# 2_4G8_2.net
KiCad netlist of a schematic drawn in EasyEDA Pro
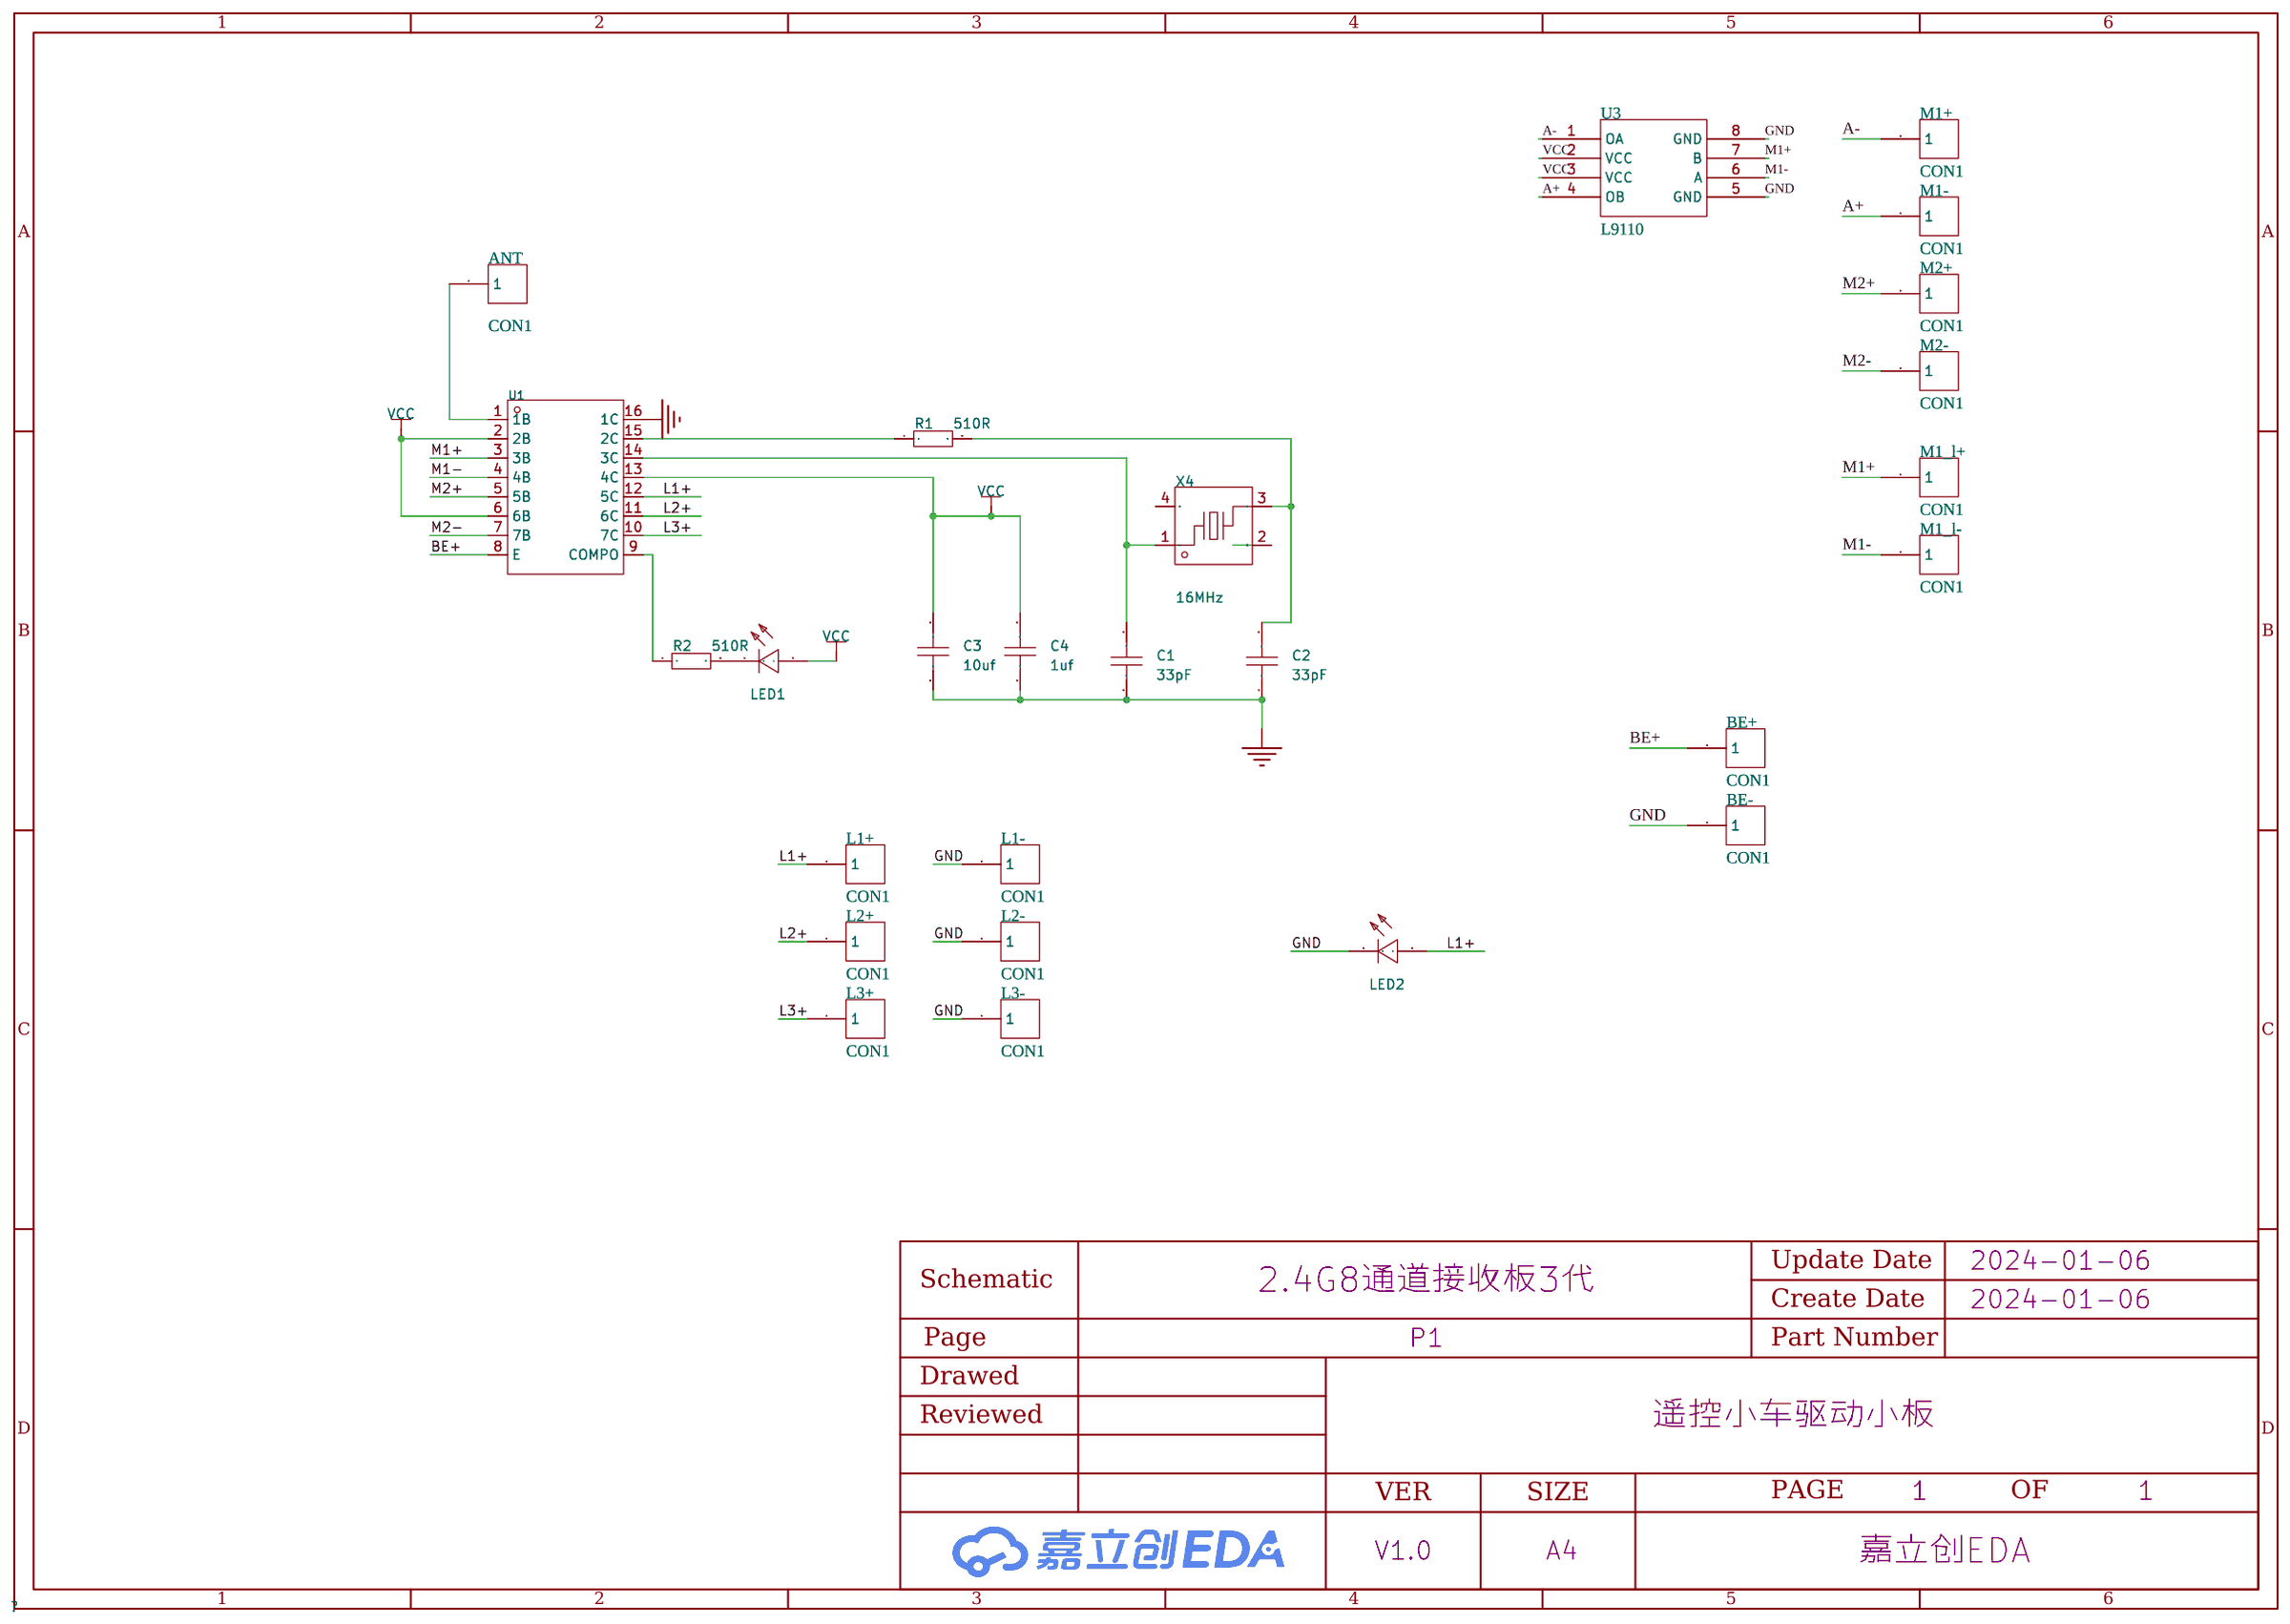
[diagram p0: schematic sheet]

(export (version "E")
  (design (tool "Eeschema 10.0.6"))
  (components
    (comp (ref "ANT")
      (value "CON1")
      (footprint "easyedapro:CON1_2")
      (libsource (lib "easyedapro") (part "CON1"))
    )
    (comp (ref "BE+")
      (value "CON1")
      (footprint "easyedapro:CON1_2")
      (libsource (lib "easyedapro") (part "CON1"))
    )
    (comp (ref "BE-")
      (value "CON1")
      (footprint "easyedapro:CON1_2")
      (libsource (lib "easyedapro") (part "CON1"))
    )
    (comp (ref "C1")
      (value "33pF")
      (footprint "easyedapro:C0603")
      (libsource (lib "easyedapro") (part "CapAcitance"))
    )
    (comp (ref "C2")
      (value "33pF")
      (footprint "easyedapro:C0603")
      (libsource (lib "easyedapro") (part "CapAcitance"))
    )
    (comp (ref "C3")
      (value "10uf")
      (footprint "easyedapro:C0603")
      (libsource (lib "easyedapro") (part "CapAcitance"))
    )
    (comp (ref "C4")
      (value "1uf")
      (footprint "easyedapro:C0603")
      (libsource (lib "easyedapro") (part "CapAcitance"))
    )
    (comp (ref "L1+")
      (value "CON1")
      (footprint "easyedapro:CON1_2")
      (libsource (lib "easyedapro") (part "CON1"))
    )
    (comp (ref "L1-")
      (value "CON1")
      (footprint "easyedapro:CON1_2")
      (libsource (lib "easyedapro") (part "CON1"))
    )
    (comp (ref "L2+")
      (value "CON1")
      (footprint "easyedapro:CON1_2")
      (libsource (lib "easyedapro") (part "CON1"))
    )
    (comp (ref "L2-")
      (value "CON1")
      (footprint "easyedapro:CON1_2")
      (libsource (lib "easyedapro") (part "CON1"))
    )
    (comp (ref "L3+")
      (value "CON1")
      (footprint "easyedapro:CON1_2")
      (libsource (lib "easyedapro") (part "CON1"))
    )
    (comp (ref "L3-")
      (value "CON1")
      (footprint "easyedapro:CON1_2")
      (libsource (lib "easyedapro") (part "CON1"))
    )
    (comp (ref "LED1")
      (value "NCD0603R1")
      (footprint "easyedapro:LED0603-RD_RED")
      (description "发光颜色:红色;功率:65mW;透镜颜色:无色透明;主波长:615nm~630nm;发光强度:80mcd~220mcd;发光角度:130°;工作温度:-30°C~+85°C;")
      (fields (field (name "Manufacturer") "国星光电"))
      (libsource (lib "easyedapro") (part "FC-DA1608HRK-620D"))
    )
    (comp (ref "LED2")
      (value "NCD0603R1")
      (footprint "easyedapro:LED0603-RD_RED")
      (description "发光颜色:红色;功率:65mW;透镜颜色:无色透明;主波长:615nm~630nm;发光强度:80mcd~220mcd;发光角度:130°;工作温度:-30°C~+85°C;")
      (fields (field (name "Manufacturer") "国星光电"))
      (libsource (lib "easyedapro") (part "FC-DA1608HRK-620D"))
    )
    (comp (ref "M1+")
      (value "CON1")
      (footprint "easyedapro:CON1_2")
      (libsource (lib "easyedapro") (part "CON1"))
    )
    (comp (ref "M1-")
      (value "CON1")
      (footprint "easyedapro:CON1_2")
      (libsource (lib "easyedapro") (part "CON1"))
    )
    (comp (ref "M1_l+")
      (value "CON1")
      (footprint "easyedapro:CON1_2")
      (libsource (lib "easyedapro") (part "CON1"))
    )
    (comp (ref "M1_l-")
      (value "CON1")
      (footprint "easyedapro:CON1_2")
      (libsource (lib "easyedapro") (part "CON1"))
    )
    (comp (ref "M2+")
      (value "CON1")
      (footprint "easyedapro:CON1_2")
      (libsource (lib "easyedapro") (part "CON1"))
    )
    (comp (ref "M2-")
      (value "CON1")
      (footprint "easyedapro:CON1_2")
      (libsource (lib "easyedapro") (part "CON1"))
    )
    (comp (ref "R1") (value "510R") (footprint "easyedapro:R0603") (libsource (lib "easyedapro") (part "电阻")))
    (comp (ref "R2") (value "510R") (footprint "easyedapro:R0603") (libsource (lib "easyedapro") (part "电阻")))
    (comp (ref "U1")
      (value "ULN2003A")
      (footprint "easyedapro:SOP-16_L10.0-W3.9-P1.27-LS6.0-BL")
      (description "开态输入电压(VI(on)@Vce,Ic):3V@2V,300mA;集射极饱和压降(VCE(sat)@Ii,Ic):900mV;开态输入电流(Ii@Vi):930uA@3.85V;")
      (fields (field (name "Manufacturer") "UMW(友台半导体)"))
      (libsource (lib "easyedapro") (part "ULN2003A_C482013"))
    )
    (comp (ref "U3")
      (value "L9110")
      (footprint "easyedapro:SOP8")
      (libsource (lib "easyedapro") (part "L9110"))
    )
    (comp (ref "X4")
      (value "16MHz")
      (footprint "easyedapro:CRYSTAL-SMD_4P-L2.0-W1.6-BL")
      (description "晶振类型:贴片无源晶振;频率:16MHz;常温频差:±10ppm;负载电容:12pF;频率稳定度(全温):±20ppm;")
      (fields
        (field (name "Manufacturer Part") "XL7EL89COI-111YLC-16M")
        (field (name "Manufacturer") "YXC(扬兴晶振)")
      )
      (libsource (lib "easyedapro") (part "XL7EL89COI-111YLC-16M"))
    )
  )
  (nets
    (net (code "1") (name "/A+") (class "Default")
      (node (ref "M1-") (pin "1") (pinfunction "1_1") (pintype "input"))
      (node (ref "U3") (pin "4") (pinfunction "OB_4") (pintype "input"))
    )
    (net (code "2") (name "/A-") (class "Default")
      (node (ref "M1+") (pin "1") (pinfunction "1_1") (pintype "input"))
      (node (ref "U3") (pin "1") (pinfunction "OA_1") (pintype "input"))
    )
    (net (code "3") (name "/BE+") (class "Default")
      (node (ref "BE+") (pin "1") (pinfunction "1_1") (pintype "input"))
      (node (ref "U1") (pin "8") (pinfunction "E_8") (pintype "input"))
    )
    (net (code "4") (name "/L1+") (class "Default")
      (node (ref "L1+") (pin "1") (pinfunction "1_1") (pintype "input"))
      (node (ref "LED2") (pin "2") (pinfunction "A_2") (pintype "input"))
      (node (ref "U1") (pin "12") (pinfunction "5C_12") (pintype "input"))
    )
    (net (code "5") (name "/L2+") (class "Default")
      (node (ref "L2+") (pin "1") (pinfunction "1_1") (pintype "input"))
      (node (ref "U1") (pin "11") (pinfunction "6C_11") (pintype "input"))
    )
    (net (code "6") (name "/L3+") (class "Default")
      (node (ref "L3+") (pin "1") (pinfunction "1_1") (pintype "input"))
      (node (ref "U1") (pin "10") (pinfunction "7C_10") (pintype "input"))
    )
    (net (code "7") (name "/M1+") (class "Default")
      (node (ref "M1_l+") (pin "1") (pinfunction "1_1") (pintype "input"))
      (node (ref "U1") (pin "3") (pinfunction "3B_3") (pintype "input"))
      (node (ref "U3") (pin "7") (pinfunction "B_7") (pintype "input"))
    )
    (net (code "8") (name "/M1-") (class "Default")
      (node (ref "M1_l-") (pin "1") (pinfunction "1_1") (pintype "input"))
      (node (ref "U1") (pin "4") (pinfunction "4B_4") (pintype "input"))
      (node (ref "U3") (pin "6") (pinfunction "A_6") (pintype "input"))
    )
    (net (code "9") (name "/M2+") (class "Default")
      (node (ref "M2+") (pin "1") (pinfunction "1_1") (pintype "input"))
      (node (ref "U1") (pin "5") (pinfunction "5B_5") (pintype "input"))
    )
    (net (code "10") (name "/M2-") (class "Default")
      (node (ref "M2-") (pin "1") (pinfunction "1_1") (pintype "input"))
      (node (ref "U1") (pin "7") (pinfunction "7B_7") (pintype "input"))
    )
    (net (code "11") (name "GND") (class "Default")
      (node (ref "BE-") (pin "1") (pinfunction "1_1") (pintype "input"))
      (node (ref "C1") (pin "1") (pinfunction "1_1") (pintype "input"))
      (node (ref "C2") (pin "1") (pinfunction "1_1") (pintype "input"))
      (node (ref "C3") (pin "1") (pinfunction "1_1") (pintype "input"))
      (node (ref "C4") (pin "1") (pinfunction "1_1") (pintype "input"))
      (node (ref "L1-") (pin "1") (pinfunction "1_1") (pintype "input"))
      (node (ref "L2-") (pin "1") (pinfunction "1_1") (pintype "input"))
      (node (ref "L3-") (pin "1") (pinfunction "1_1") (pintype "input"))
      (node (ref "LED2") (pin "1") (pinfunction "K_1") (pintype "input"))
      (node (ref "U1") (pin "16") (pinfunction "1C_16") (pintype "input"))
      (node (ref "U3") (pin "5") (pinfunction "GND_5") (pintype "input"))
      (node (ref "U3") (pin "8") (pinfunction "GND_8") (pintype "input"))
    )
    (net (code "12") (name "Net-(C2-Pad2)") (class "Default")
      (node (ref "C2") (pin "2") (pinfunction "2_2") (pintype "input"))
      (node (ref "R1") (pin "2") (pinfunction "2_2") (pintype "input"))
      (node (ref "X4") (pin "3") (pinfunction "3_3") (pintype "input"))
    )
    (net (code "13") (name "Net-(LED1-K)") (class "Default")
      (node (ref "LED1") (pin "1") (pinfunction "K_1") (pintype "input"))
      (node (ref "R2") (pin "2") (pinfunction "2_2") (pintype "input"))
    )
    (net (code "14") (name "Net-(U1-1B)") (class "Default")
      (node (ref "ANT") (pin "1") (pinfunction "1_1") (pintype "input"))
      (node (ref "U1") (pin "1") (pinfunction "1B_1") (pintype "input"))
    )
    (net (code "15") (name "Net-(U1-2C)") (class "Default")
      (node (ref "R1") (pin "1") (pinfunction "1_1") (pintype "input"))
      (node (ref "U1") (pin "15") (pinfunction "2C_15") (pintype "input"))
    )
    (net (code "16") (name "Net-(U1-3C)") (class "Default")
      (node (ref "C1") (pin "2") (pinfunction "2_2") (pintype "input"))
      (node (ref "U1") (pin "14") (pinfunction "3C_14") (pintype "input"))
      (node (ref "X4") (pin "1") (pinfunction "1_1") (pintype "input"))
    )
    (net (code "17") (name "Net-(U1-COMPO)") (class "Default")
      (node (ref "R2") (pin "1") (pinfunction "1_1") (pintype "input"))
      (node (ref "U1") (pin "9") (pinfunction "COMPO_9") (pintype "input"))
    )
    (net (code "18") (name "VCC") (class "Default")
      (node (ref "C3") (pin "2") (pinfunction "2_2") (pintype "input"))
      (node (ref "C4") (pin "2") (pinfunction "2_2") (pintype "input"))
      (node (ref "LED1") (pin "2") (pinfunction "A_2") (pintype "input"))
      (node (ref "U1") (pin "13") (pinfunction "4C_13") (pintype "input"))
      (node (ref "U1") (pin "2") (pinfunction "2B_2") (pintype "input"))
      (node (ref "U1") (pin "6") (pinfunction "6B_6") (pintype "input"))
      (node (ref "U3") (pin "2") (pinfunction "VCC_2") (pintype "input"))
      (node (ref "U3") (pin "3") (pinfunction "VCC_3") (pintype "input"))
    )
    (net (code "19") (name "unconnected-(X4-GND-Pad2)") (class "Default")
      (node (ref "X4") (pin "2") (pinfunction "GND_2") (pintype "input"))
    )
    (net (code "20") (name "unconnected-(X4-GND-Pad4)") (class "Default")
      (node (ref "X4") (pin "4") (pinfunction "GND_4") (pintype "input"))
    )
  )
)
